# fm.net
KiCad netlist of a schematic drawn in EAGLE
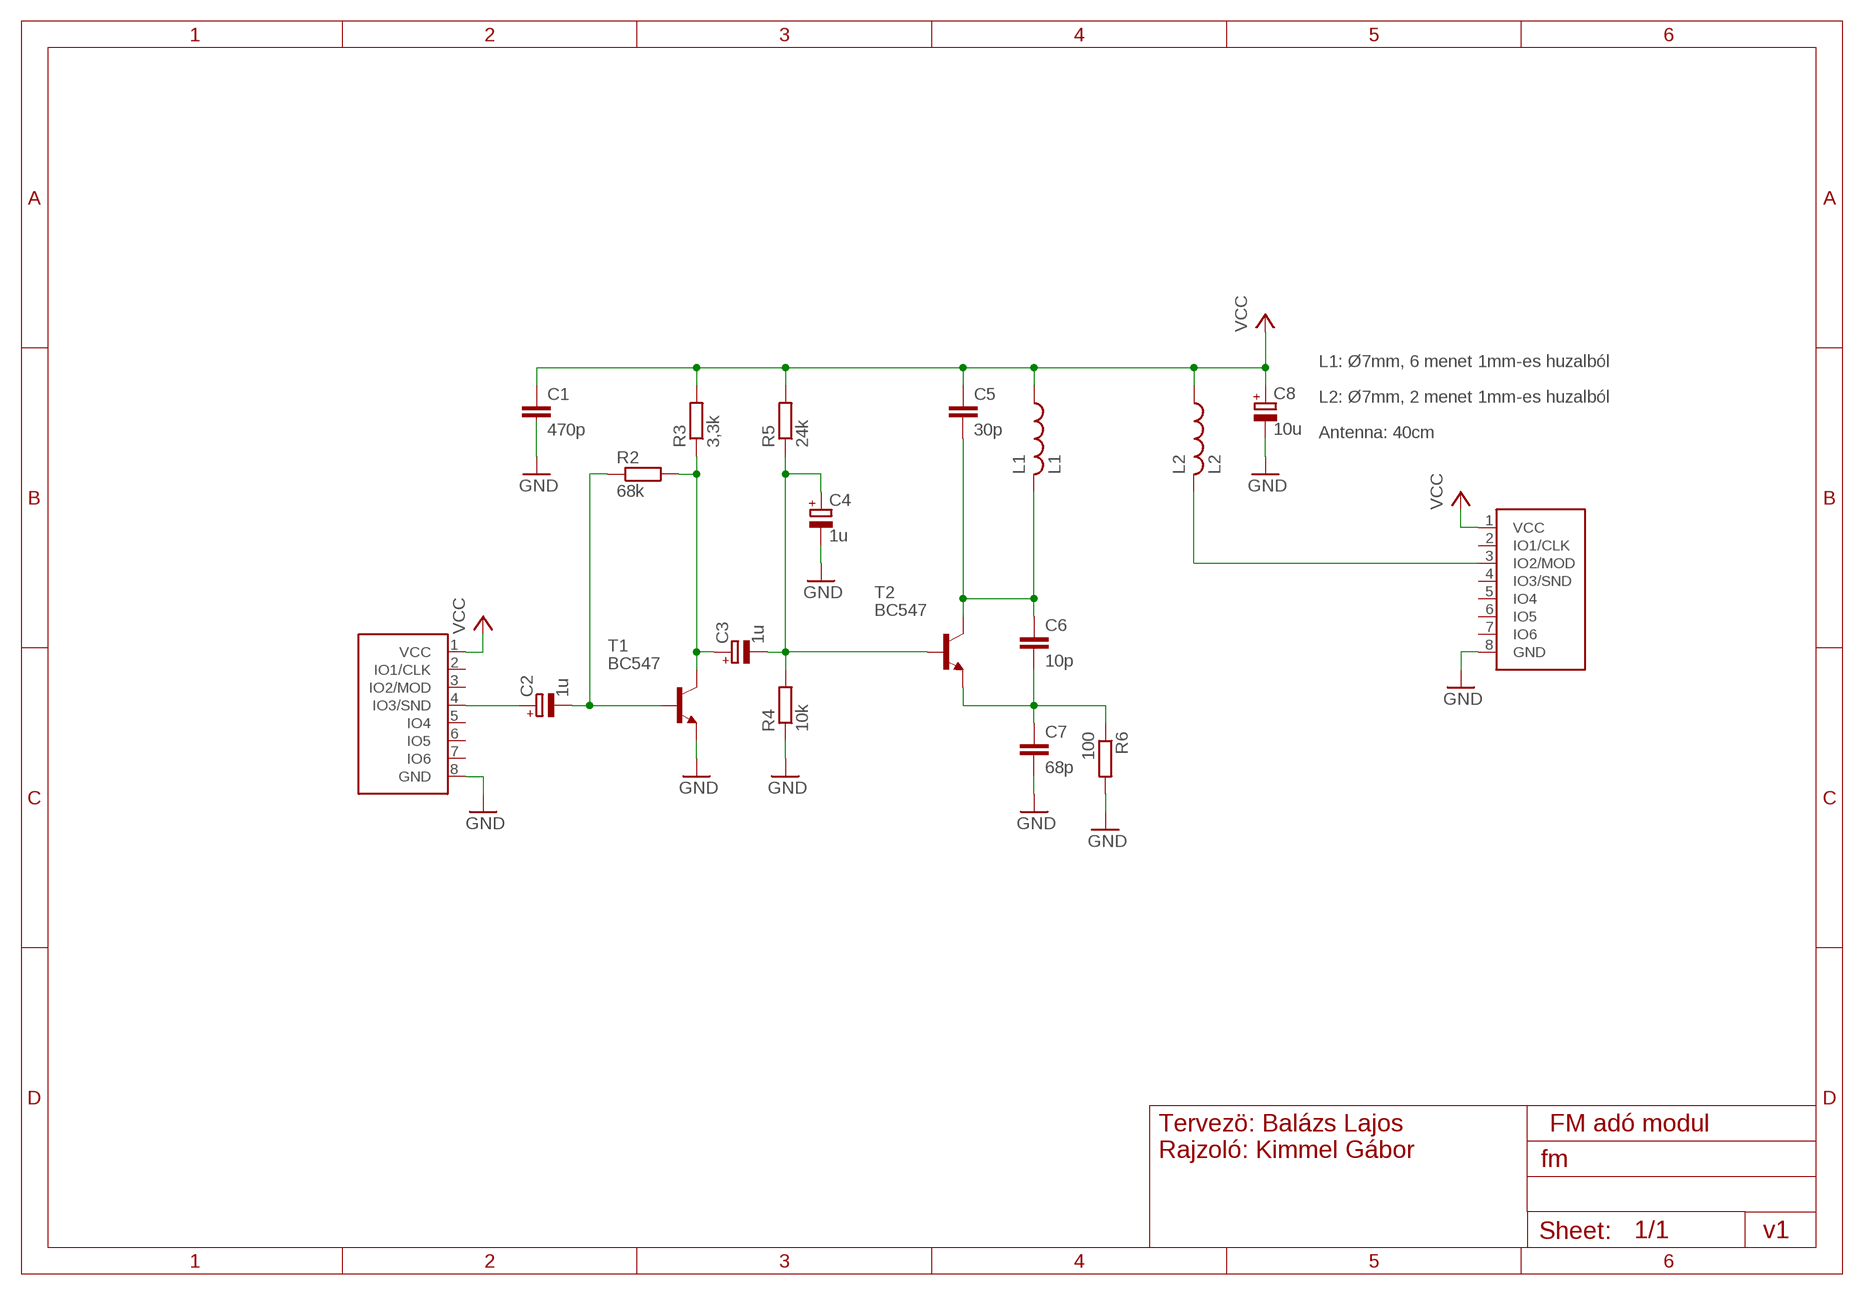
[diagram p0: schematic, sheet 1]

(export (version "E")
  (design (tool "Eeschema 10.0.6"))
  (components
    (comp (ref "C1")
      (value "470p")
      (footprint "eagle-import:C075-032X103")
      (libsource (lib "eagle-import") (part "C-EU075-032X103"))
    )
    (comp (ref "C2")
      (value "1u")
      (footprint "eagle-import:E2,5-7")
      (libsource (lib "eagle-import") (part "CPOL-EUE2.5-7"))
    )
    (comp (ref "C3")
      (value "1u")
      (footprint "eagle-import:E2,5-7")
      (libsource (lib "eagle-import") (part "CPOL-EUE2.5-7"))
    )
    (comp (ref "C4")
      (value "1u")
      (footprint "eagle-import:E2,5-7")
      (libsource (lib "eagle-import") (part "CPOL-EUE2.5-7"))
    )
    (comp (ref "C5")
      (value "30p")
      (footprint "eagle-import:C075-032X103")
      (libsource (lib "eagle-import") (part "C-EU075-032X103"))
    )
    (comp (ref "C6")
      (value "10p")
      (footprint "eagle-import:C075-032X103")
      (libsource (lib "eagle-import") (part "C-EU075-032X103"))
    )
    (comp (ref "C7")
      (value "68p")
      (footprint "eagle-import:C075-032X103")
      (libsource (lib "eagle-import") (part "C-EU075-032X103"))
    )
    (comp (ref "C8")
      (value "10u")
      (footprint "eagle-import:E2,5-7")
      (libsource (lib "eagle-import") (part "CPOL-EUE2.5-7"))
    )
    (comp (ref "L1")
      (value "L1")
      (footprint "eagle-import:0207_7")
      (libsource (lib "eagle-import") (part "L-US0207/7"))
    )
    (comp (ref "L2")
      (value "L2")
      (footprint "eagle-import:0207_7")
      (libsource (lib "eagle-import") (part "L-US0207/7"))
    )
    (comp (ref "R2")
      (value "68k")
      (footprint "eagle-import:0309_12")
      (libsource (lib "eagle-import") (part "R-EU_0309/12"))
    )
    (comp (ref "R3")
      (value "3,3k")
      (footprint "eagle-import:0309_12")
      (libsource (lib "eagle-import") (part "R-EU_0309/12"))
    )
    (comp (ref "R4")
      (value "10k")
      (footprint "eagle-import:0309_12")
      (libsource (lib "eagle-import") (part "R-EU_0309/12"))
    )
    (comp (ref "R5")
      (value "24k")
      (footprint "eagle-import:0309_12")
      (libsource (lib "eagle-import") (part "R-EU_0309/12"))
    )
    (comp (ref "R6")
      (value "100")
      (footprint "eagle-import:0309_12")
      (libsource (lib "eagle-import") (part "R-EU_0309/12"))
    )
    (comp (ref "T1")
      (value "BC547")
      (footprint "eagle-import:TO92-CBE")
      (libsource (lib "eagle-import") (part "-NPN-TO92-CBEBC237"))
    )
    (comp (ref "T2")
      (value "BC547")
      (footprint "eagle-import:TO92-CBE")
      (libsource (lib "eagle-import") (part "-NPN-TO92-CBEBC237"))
    )
    (comp (ref "U$1")
      (value "GANZ-CONNECTOR")
      (footprint "eagle-import:FE08W")
      (libsource (lib "eagle-import") (part "GANZ-CONNECTOR"))
    )
    (comp (ref "U$2")
      (value "GANZ-CONNECTOR-OUT")
      (footprint "eagle-import:MA08-1W")
      (libsource (lib "eagle-import") (part "GANZ-CONNECTOR-OUT"))
    )
  )
  (nets
    (net (code "1") (name "GND") (class "Default")
      (node (ref "C1") (pin "2") (pinfunction "2_2") (pintype "passive"))
      (node (ref "C4") (pin "-") (pinfunction "-_-") (pintype "passive"))
      (node (ref "C7") (pin "2") (pinfunction "2_2") (pintype "passive"))
      (node (ref "C8") (pin "-") (pinfunction "-_-") (pintype "passive"))
      (node (ref "R4") (pin "1") (pinfunction "1_1") (pintype "passive"))
      (node (ref "R6") (pin "2") (pinfunction "2_2") (pintype "passive"))
      (node (ref "T1") (pin "E") (pinfunction "E_E") (pintype "passive"))
      (node (ref "U$1") (pin "8") (pinfunction "GND_8") (pintype "bidirectional"))
      (node (ref "U$2") (pin "8") (pinfunction "GND_8") (pintype "bidirectional"))
    )
    (net (code "2") (name "Net-(C2-Pad-)") (class "Default")
      (node (ref "C2") (pin "-") (pinfunction "-_-") (pintype "passive"))
      (node (ref "R2") (pin "1") (pinfunction "1_1") (pintype "passive"))
      (node (ref "T1") (pin "B") (pinfunction "B_B") (pintype "passive"))
    )
    (net (code "3") (name "Net-(C3-Pad+)") (class "Default")
      (node (ref "C3") (pin "+") (pinfunction "+_+") (pintype "passive"))
      (node (ref "R2") (pin "2") (pinfunction "2_2") (pintype "passive"))
      (node (ref "R3") (pin "1") (pinfunction "1_1") (pintype "passive"))
      (node (ref "T1") (pin "C") (pinfunction "C_C") (pintype "passive"))
    )
    (net (code "4") (name "Net-(C3-Pad-)") (class "Default")
      (node (ref "C3") (pin "-") (pinfunction "-_-") (pintype "passive"))
      (node (ref "C4") (pin "+") (pinfunction "+_+") (pintype "passive"))
      (node (ref "R4") (pin "2") (pinfunction "2_2") (pintype "passive"))
      (node (ref "R5") (pin "1") (pinfunction "1_1") (pintype "passive"))
      (node (ref "T2") (pin "B") (pinfunction "B_B") (pintype "passive"))
    )
    (net (code "5") (name "Net-(C5-Pad2)") (class "Default")
      (node (ref "C5") (pin "2") (pinfunction "2_2") (pintype "passive"))
      (node (ref "C6") (pin "1") (pinfunction "1_1") (pintype "passive"))
      (node (ref "L1") (pin "2") (pinfunction "2_2") (pintype "passive"))
      (node (ref "T2") (pin "C") (pinfunction "C_C") (pintype "passive"))
    )
    (net (code "6") (name "Net-(C6-Pad2)") (class "Default")
      (node (ref "C6") (pin "2") (pinfunction "2_2") (pintype "passive"))
      (node (ref "C7") (pin "1") (pinfunction "1_1") (pintype "passive"))
      (node (ref "R6") (pin "1") (pinfunction "1_1") (pintype "passive"))
      (node (ref "T2") (pin "E") (pinfunction "E_E") (pintype "passive"))
    )
    (net (code "7") (name "Net-(U$1-IO3{slash}SND)") (class "Default")
      (node (ref "C2") (pin "+") (pinfunction "+_+") (pintype "passive"))
      (node (ref "U$1") (pin "4") (pinfunction "IO3/SND_4") (pintype "bidirectional"))
    )
    (net (code "8") (name "Net-(U$2-IO2{slash}MOD)") (class "Default")
      (node (ref "L2") (pin "2") (pinfunction "2_2") (pintype "passive"))
      (node (ref "U$2") (pin "3") (pinfunction "IO2/MOD_3") (pintype "bidirectional"))
    )
    (net (code "9") (name "VCC") (class "Default")
      (node (ref "C1") (pin "1") (pinfunction "1_1") (pintype "passive"))
      (node (ref "C5") (pin "1") (pinfunction "1_1") (pintype "passive"))
      (node (ref "C8") (pin "+") (pinfunction "+_+") (pintype "passive"))
      (node (ref "L1") (pin "1") (pinfunction "1_1") (pintype "passive"))
      (node (ref "L2") (pin "1") (pinfunction "1_1") (pintype "passive"))
      (node (ref "R3") (pin "2") (pinfunction "2_2") (pintype "passive"))
      (node (ref "R5") (pin "2") (pinfunction "2_2") (pintype "passive"))
      (node (ref "U$1") (pin "1") (pinfunction "VCC_1") (pintype "bidirectional"))
      (node (ref "U$2") (pin "1") (pinfunction "VCC_1") (pintype "bidirectional"))
    )
    (net (code "10") (name "unconnected-(U$1-IO1{slash}CLK-Pad2)") (class "Default")
      (node (ref "U$1") (pin "2") (pinfunction "IO1/CLK_2") (pintype "bidirectional"))
    )
    (net (code "11") (name "unconnected-(U$1-IO2{slash}MOD-Pad3)") (class "Default")
      (node (ref "U$1") (pin "3") (pinfunction "IO2/MOD_3") (pintype "bidirectional"))
    )
    (net (code "12") (name "unconnected-(U$1-IO4-Pad5)") (class "Default")
      (node (ref "U$1") (pin "5") (pinfunction "IO4_5") (pintype "bidirectional"))
    )
    (net (code "13") (name "unconnected-(U$1-IO5-Pad6)") (class "Default")
      (node (ref "U$1") (pin "6") (pinfunction "IO5_6") (pintype "bidirectional"))
    )
    (net (code "14") (name "unconnected-(U$1-IO6-Pad7)") (class "Default")
      (node (ref "U$1") (pin "7") (pinfunction "IO6_7") (pintype "bidirectional"))
    )
    (net (code "15") (name "unconnected-(U$2-IO1{slash}CLK-Pad2)") (class "Default")
      (node (ref "U$2") (pin "2") (pinfunction "IO1/CLK_2") (pintype "bidirectional"))
    )
    (net (code "16") (name "unconnected-(U$2-IO3{slash}SND-Pad4)") (class "Default")
      (node (ref "U$2") (pin "4") (pinfunction "IO3/SND_4") (pintype "bidirectional"))
    )
    (net (code "17") (name "unconnected-(U$2-IO4-Pad5)") (class "Default")
      (node (ref "U$2") (pin "5") (pinfunction "IO4_5") (pintype "bidirectional"))
    )
    (net (code "18") (name "unconnected-(U$2-IO5-Pad6)") (class "Default")
      (node (ref "U$2") (pin "6") (pinfunction "IO5_6") (pintype "bidirectional"))
    )
    (net (code "19") (name "unconnected-(U$2-IO6-Pad7)") (class "Default")
      (node (ref "U$2") (pin "7") (pinfunction "IO6_7") (pintype "bidirectional"))
    )
  )
)
